# IRF7317_TC4427.net
KiCad netlist of a schematic drawn in Altium Designer
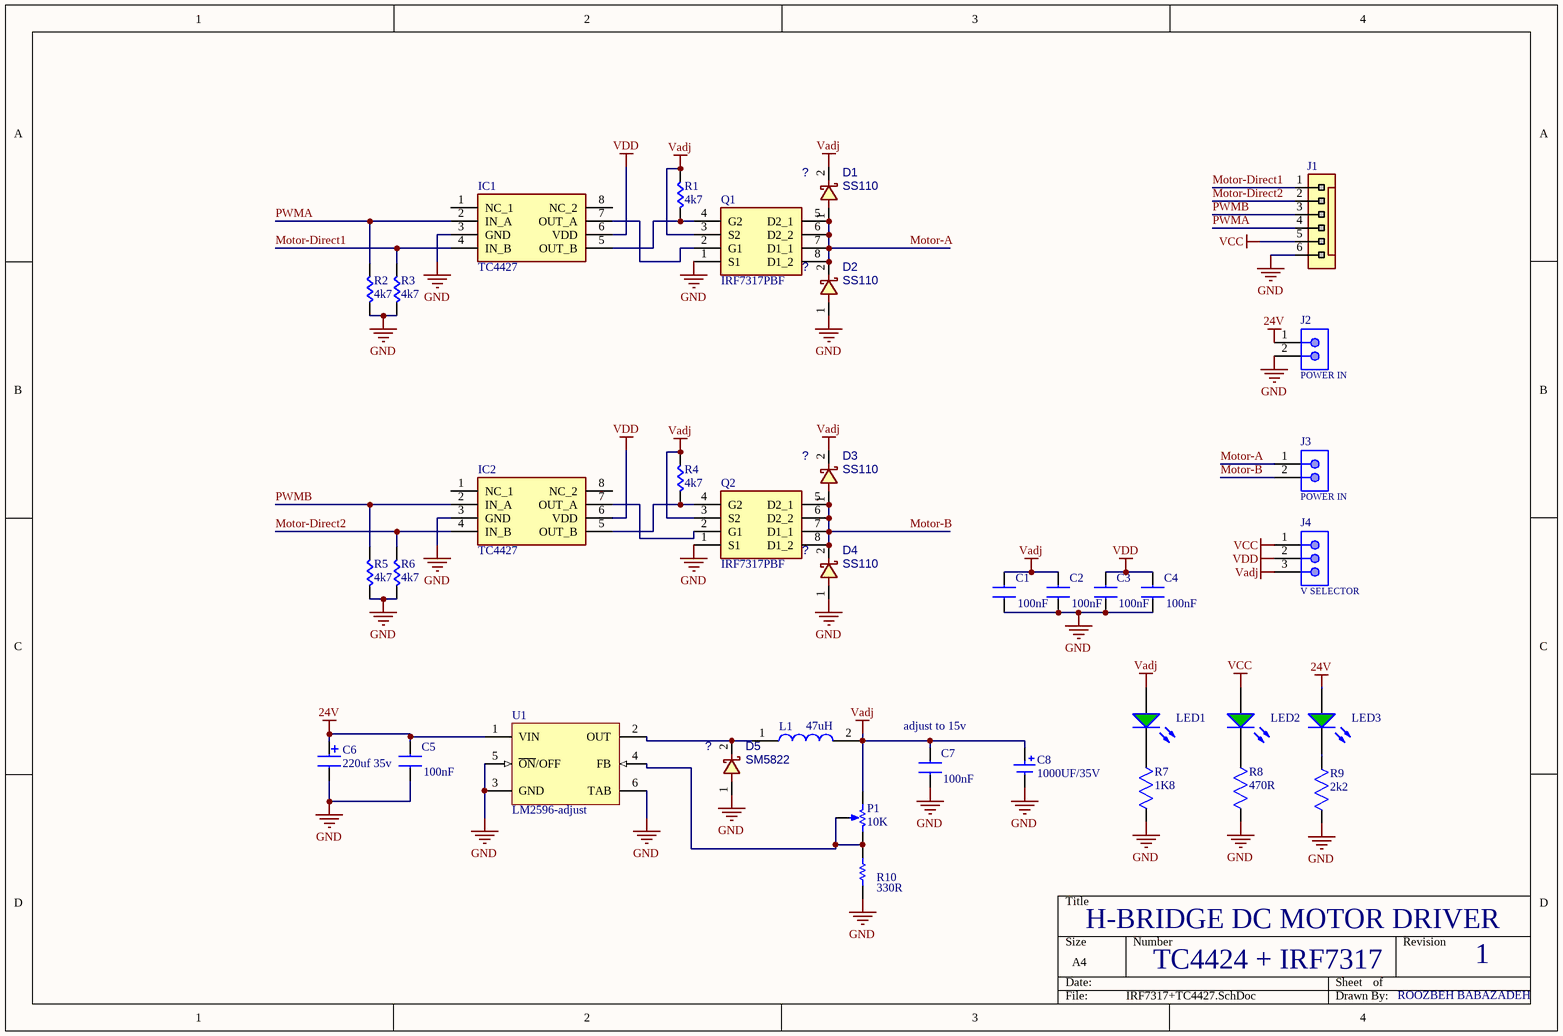
[diagram p0: IRF7317+TC4427.SchDoc]

(export (version "E")
  (design (tool "Eeschema 10.0.6"))
  (components
    (comp (ref "C1") (value "100nF") (footprint "C0805") (libsource (lib "OTHER") (part "C")))
    (comp (ref "C2") (value "100nF") (footprint "C0805") (libsource (lib "OTHER") (part "C")))
    (comp (ref "C3") (value "100nF") (footprint "C0805") (libsource (lib "OTHER") (part "C")))
    (comp (ref "C4") (value "100nF") (footprint "C0805") (libsource (lib "OTHER") (part "C")))
    (comp (ref "C5") (value "100nF") (footprint "C0805") (libsource (lib "OTHER") (part "C")))
    (comp (ref "C6") (value "220uf 35v") (footprint "C_EL_10X12") (libsource (lib "OTHER") (part "CAP3528")))
    (comp (ref "C7") (value "100nF") (footprint "C0805") (libsource (lib "OTHER") (part "C")))
    (comp (ref "C8")
      (value "1000UF/35V")
      (footprint "C_EL_12X25")
      (libsource (lib "OTHER") (part "CAP_ELECTRO_POLIMER"))
    )
    (comp (ref "D1")
      (value "SS110")
      (footprint "D_SMA")
      (description "DIODE, SCHOTTKY, 40V, 1A")
      (fields
        (field (name "MANF") "DIODES")
        (field (name "MANF_P#") "1N5819HW-7-F")
        (field (name "ALTIUM_VALUE") "?")
      )
      (libsource (lib "diode") (part "SCHOTTKY"))
    )
    (comp (ref "D2")
      (value "SS110")
      (footprint "D_SMA")
      (description "DIODE, SCHOTTKY, 40V, 1A")
      (fields
        (field (name "MANF") "DIODES")
        (field (name "MANF_P#") "1N5819HW-7-F")
        (field (name "ALTIUM_VALUE") "?")
      )
      (libsource (lib "diode") (part "SCHOTTKY"))
    )
    (comp (ref "D3")
      (value "SS110")
      (footprint "D_SMA")
      (description "DIODE, SCHOTTKY, 40V, 1A")
      (fields
        (field (name "MANF") "DIODES")
        (field (name "MANF_P#") "1N5819HW-7-F")
        (field (name "ALTIUM_VALUE") "?")
      )
      (libsource (lib "diode") (part "SCHOTTKY"))
    )
    (comp (ref "D4")
      (value "SS110")
      (footprint "D_SMA")
      (description "DIODE, SCHOTTKY, 40V, 1A")
      (fields
        (field (name "MANF") "DIODES")
        (field (name "MANF_P#") "1N5819HW-7-F")
        (field (name "ALTIUM_VALUE") "?")
      )
      (libsource (lib "diode") (part "SCHOTTKY"))
    )
    (comp (ref "D5")
      (value "SM5822")
      (footprint "D_SMB")
      (description "DIODE, SCHOTTKY, 40V, 1A")
      (fields
        (field (name "MANF") "DIODES")
        (field (name "MANF_P#") "1N5819HW-7-F")
        (field (name "ALTIUM_VALUE") "?")
      )
      (libsource (lib "diode") (part "SCHOTTKY"))
    )
    (comp (ref "IC1")
      (value "TC4427")
      (footprint "SO_8")
      (description "Integrated Circuit")
      (fields
        (field (name "MANUFACTURER_PART_NUMBER") "TC4427EOA713")
        (field (name "MOUSER PART NUMBER") "579-TC4427EOA713")
      )
      (libsource (lib "*") (part "TC4427EOA713"))
    )
    (comp (ref "IC2")
      (value "TC4427")
      (footprint "SO_8")
      (description "Integrated Circuit")
      (fields
        (field (name "MANUFACTURER_PART_NUMBER") "TC4427EOA713")
        (field (name "MOUSER PART NUMBER") "579-TC4427EOA713")
      )
      (libsource (lib "*") (part "TC4427EOA713"))
    )
    (comp (ref "J1")
      (value "HDRWF_6")
      (footprint "WF_6")
      (description "Header, WF, Pitch: 2.54mm")
      (libsource (lib "xh-xhr-wf-hhdr-hh6r") (part "HDRWF_6"))
    )
    (comp (ref "J2")
      (value "POWER IN")
      (footprint "PWL_2")
      (description "WR-PHD Pin Header, THT, pitch 2.54mm, Single Row, Vertical, 2pin")
      (fields (field (name "PART NUMBER") "61300211121") (field (name "PUBLISHER") "Wurth Elektronik"))
      (libsource (lib "sip m") (part "sip 2"))
    )
    (comp (ref "J3")
      (value "POWER IN")
      (footprint "PWL_2")
      (description "WR-PHD Pin Header, THT, pitch 2.54mm, Single Row, Vertical, 2pin")
      (fields (field (name "PART NUMBER") "61300211121") (field (name "PUBLISHER") "Wurth Elektronik"))
      (libsource (lib "sip m") (part "sip 2"))
    )
    (comp (ref "J4")
      (value "V SELECTOR")
      (footprint "3_SIP")
      (description "WR-PHD Pin Header, THT, pitch 2.54mm, Single Row, Vertical, 3pin")
      (fields (field (name "PART NUMBER") "61300311121") (field (name "PUBLISHER") "Wurth Elektronik"))
      (libsource (lib "sip m") (part "sip 3"))
    )
    (comp (ref "L1")
      (value "47uH")
      (footprint "CDRH127LDNP560MC-12*12")
      (description "Inductor")
      (fields
        (field (name "MANUFACTURER_PART_NUMBER") "CDRH127/LDNP-560MC")
        (field (name "MOUSER PART NUMBER") "851-CDRH127LDNP560MC")
      )
      (libsource (lib "*") (part "CDRH127_LDNP-560MC"))
    )
    (comp (ref "LED1") (value "~") (footprint "LED1206RED") (libsource (lib "OTHER") (part "LED3mm")))
    (comp (ref "LED2") (value "~") (footprint "LED1206RED") (libsource (lib "OTHER") (part "LED3mm")))
    (comp (ref "LED3") (value "~") (footprint "LED1206RED") (libsource (lib "OTHER") (part "LED3mm")))
    (comp (ref "P1")
      (value "10K")
      (footprint "POT_3296W")
      (description "Potentiometer")
      (libsource (lib "My_LIB") (part "Multi-Turn"))
    )
    (comp (ref "Q1")
      (value "IRF7317PBF")
      (footprint "SO_8")
      (description "Transistor")
      (fields (field (name "MOUSER PART NUMBER") "942-IRF7317PBF"))
      (libsource (lib "*") (part "IRF7317PBF"))
    )
    (comp (ref "Q2")
      (value "IRF7317PBF")
      (footprint "SO_8")
      (description "Transistor")
      (fields (field (name "MOUSER PART NUMBER") "942-IRF7317PBF"))
      (libsource (lib "*") (part "IRF7317PBF"))
    )
    (comp (ref "R1") (value "4k7") (footprint "R0805") (libsource (lib "OTHER") (part "R")))
    (comp (ref "R2") (value "4k7") (footprint "R0805") (libsource (lib "OTHER") (part "R")))
    (comp (ref "R3") (value "4k7") (footprint "R0805") (libsource (lib "OTHER") (part "R")))
    (comp (ref "R4") (value "4k7") (footprint "R0805") (libsource (lib "OTHER") (part "R")))
    (comp (ref "R5") (value "4k7") (footprint "R0805") (libsource (lib "OTHER") (part "R")))
    (comp (ref "R6") (value "4k7") (footprint "R0805") (libsource (lib "OTHER") (part "R")))
    (comp (ref "R7") (value "1K8") (footprint "R0805") (libsource (lib "") (part "R_1")))
    (comp (ref "R8") (value "470R") (footprint "R0805") (libsource (lib "") (part "R_1")))
    (comp (ref "R9") (value "2k2") (footprint "R0805") (libsource (lib "") (part "R_1")))
    (comp (ref "R10")
      (value "330R")
      (footprint "R0805")
      (description "Resistor")
      (fields (field (name "PUBLISHER") "Altium Limited"))
      (libsource (lib "Miscellaneous Devices") (part "Res1"))
    )
    (comp (ref "U1")
      (value "LM2596-adjust")
      (footprint "to-263-5 5d2pak LM2596S")
      (libsource (lib "POWER") (part "LM2596s"))
    )
  )
  (nets
    (net (code "1") (name "/Motor-A") (class "Default")
      (node (ref "D1") (pin "1") (pinfunction "1_1") (pintype "passive"))
      (node (ref "D2") (pin "2") (pinfunction "2_2") (pintype "passive"))
      (node (ref "J3") (pin "1") (pinfunction "1_1") (pintype "passive"))
      (node (ref "Q1") (pin "5") (pinfunction "D2_1_5") (pintype "passive"))
      (node (ref "Q1") (pin "6") (pinfunction "D2_2_6") (pintype "passive"))
      (node (ref "Q1") (pin "7") (pinfunction "D1_1_7") (pintype "passive"))
      (node (ref "Q1") (pin "8") (pinfunction "D1_2_8") (pintype "passive"))
    )
    (net (code "2") (name "/Motor-B") (class "Default")
      (node (ref "D3") (pin "1") (pinfunction "1_1") (pintype "passive"))
      (node (ref "D4") (pin "2") (pinfunction "2_2") (pintype "passive"))
      (node (ref "J3") (pin "2") (pinfunction "2_2") (pintype "passive"))
      (node (ref "Q2") (pin "5") (pinfunction "D2_1_5") (pintype "passive"))
      (node (ref "Q2") (pin "6") (pinfunction "D2_2_6") (pintype "passive"))
      (node (ref "Q2") (pin "7") (pinfunction "D1_1_7") (pintype "passive"))
      (node (ref "Q2") (pin "8") (pinfunction "D1_2_8") (pintype "passive"))
    )
    (net (code "3") (name "/Motor-Direct1") (class "Default")
      (node (ref "IC1") (pin "4") (pinfunction "IN_B_4") (pintype "passive"))
      (node (ref "J1") (pin "1") (pinfunction "1_1") (pintype "passive"))
      (node (ref "R3") (pin "1") (pintype "passive"))
    )
    (net (code "4") (name "/Motor-Direct2") (class "Default")
      (node (ref "IC2") (pin "4") (pinfunction "IN_B_4") (pintype "passive"))
      (node (ref "J1") (pin "2") (pinfunction "2_2") (pintype "passive"))
      (node (ref "R6") (pin "1") (pintype "passive"))
    )
    (net (code "5") (name "/PWMA") (class "Default")
      (node (ref "IC1") (pin "2") (pinfunction "IN_A_2") (pintype "passive"))
      (node (ref "J1") (pin "4") (pinfunction "4_4") (pintype "passive"))
      (node (ref "R2") (pin "1") (pintype "passive"))
    )
    (net (code "6") (name "/PWMB") (class "Default")
      (node (ref "IC2") (pin "2") (pinfunction "IN_A_2") (pintype "passive"))
      (node (ref "J1") (pin "3") (pinfunction "3_3") (pintype "passive"))
      (node (ref "R5") (pin "1") (pintype "passive"))
    )
    (net (code "7") (name "24V") (class "Default")
      (node (ref "C5") (pin "2") (pintype "passive"))
      (node (ref "C6") (pin "1") (pinfunction "1_1") (pintype "passive"))
      (node (ref "J2") (pin "1") (pinfunction "1_1") (pintype "passive"))
      (node (ref "LED3") (pin "1") (pinfunction "A_1") (pintype "passive"))
      (node (ref "U1") (pin "1") (pinfunction "VIN_1") (pintype "power_in"))
    )
    (net (code "8") (name "GND") (class "Default")
      (node (ref "C1") (pin "1") (pintype "passive"))
      (node (ref "C2") (pin "1") (pintype "passive"))
      (node (ref "C3") (pin "1") (pintype "passive"))
      (node (ref "C4") (pin "1") (pintype "passive"))
      (node (ref "C5") (pin "1") (pintype "passive"))
      (node (ref "C6") (pin "2") (pinfunction "2_2") (pintype "passive"))
      (node (ref "C7") (pin "1") (pintype "passive"))
      (node (ref "C8") (pin "2") (pinfunction "2_2") (pintype "passive"))
      (node (ref "D2") (pin "1") (pinfunction "1_1") (pintype "passive"))
      (node (ref "D4") (pin "1") (pinfunction "1_1") (pintype "passive"))
      (node (ref "D5") (pin "1") (pinfunction "1_1") (pintype "passive"))
      (node (ref "IC1") (pin "3") (pinfunction "GND_3") (pintype "passive"))
      (node (ref "IC2") (pin "3") (pinfunction "GND_3") (pintype "passive"))
      (node (ref "J1") (pin "6") (pinfunction "6_6") (pintype "passive"))
      (node (ref "J2") (pin "2") (pinfunction "2_2") (pintype "passive"))
      (node (ref "Q1") (pin "1") (pinfunction "S1_1") (pintype "passive"))
      (node (ref "Q2") (pin "1") (pinfunction "S1_1") (pintype "passive"))
      (node (ref "R10") (pin "1") (pinfunction "1_1") (pintype "passive"))
      (node (ref "R2") (pin "2") (pintype "passive"))
      (node (ref "R3") (pin "2") (pintype "passive"))
      (node (ref "R5") (pin "2") (pintype "passive"))
      (node (ref "R6") (pin "2") (pintype "passive"))
      (node (ref "R7") (pin "2") (pintype "passive"))
      (node (ref "R8") (pin "2") (pintype "passive"))
      (node (ref "R9") (pin "2") (pintype "passive"))
      (node (ref "U1") (pin "3") (pinfunction "GND_3") (pintype "power_in"))
      (node (ref "U1") (pin "5") (pinfunction "~{ON}/OFF_5") (pintype "input"))
      (node (ref "U1") (pin "6") (pinfunction "TAB_6") (pintype "power_in"))
    )
    (net (code "9") (name "Net-(IC1-OUT_A)") (class "Default")
      (node (ref "IC1") (pin "7") (pinfunction "OUT_A_7") (pintype "passive"))
      (node (ref "Q1") (pin "2") (pinfunction "G1_2") (pintype "passive"))
    )
    (net (code "10") (name "Net-(IC1-OUT_B)") (class "Default")
      (node (ref "IC1") (pin "5") (pinfunction "OUT_B_5") (pintype "passive"))
      (node (ref "Q1") (pin "4") (pinfunction "G2_4") (pintype "passive"))
      (node (ref "R1") (pin "2") (pintype "passive"))
    )
    (net (code "11") (name "Net-(IC2-OUT_A)") (class "Default")
      (node (ref "IC2") (pin "7") (pinfunction "OUT_A_7") (pintype "passive"))
      (node (ref "Q2") (pin "2") (pinfunction "G1_2") (pintype "passive"))
    )
    (net (code "12") (name "Net-(IC2-OUT_B)") (class "Default")
      (node (ref "IC2") (pin "5") (pinfunction "OUT_B_5") (pintype "passive"))
      (node (ref "Q2") (pin "4") (pinfunction "G2_4") (pintype "passive"))
      (node (ref "R4") (pin "2") (pintype "passive"))
    )
    (net (code "13") (name "Net-(LED1-K)") (class "Default")
      (node (ref "LED1") (pin "2") (pinfunction "K_2") (pintype "passive"))
      (node (ref "R7") (pin "1") (pintype "passive"))
    )
    (net (code "14") (name "Net-(LED2-K)") (class "Default")
      (node (ref "LED2") (pin "2") (pinfunction "K_2") (pintype "passive"))
      (node (ref "R8") (pin "1") (pintype "passive"))
    )
    (net (code "15") (name "Net-(LED3-K)") (class "Default")
      (node (ref "LED3") (pin "2") (pinfunction "K_2") (pintype "passive"))
      (node (ref "R9") (pin "1") (pintype "passive"))
    )
    (net (code "16") (name "Net-(P1-TAP)") (class "Default")
      (node (ref "P1") (pin "1") (pinfunction "TOP_1") (pintype "passive"))
      (node (ref "P1") (pin "2") (pinfunction "TAP_2") (pintype "passive"))
      (node (ref "R10") (pin "2") (pinfunction "2_2") (pintype "passive"))
      (node (ref "U1") (pin "4") (pinfunction "FB_4") (pintype "input"))
    )
    (net (code "17") (name "Net-(U1-OUT)") (class "Default")
      (node (ref "D5") (pin "2") (pinfunction "2_2") (pintype "passive"))
      (node (ref "L1") (pin "1") (pinfunction "1_1") (pintype "passive"))
      (node (ref "U1") (pin "2") (pinfunction "OUT_2") (pintype "power_in"))
    )
    (net (code "18") (name "VCC") (class "Default")
      (node (ref "J1") (pin "5") (pinfunction "5_5") (pintype "passive"))
      (node (ref "J4") (pin "1") (pinfunction "1_1") (pintype "passive"))
      (node (ref "LED2") (pin "1") (pinfunction "A_1") (pintype "passive"))
    )
    (net (code "19") (name "VDD") (class "Default")
      (node (ref "C3") (pin "2") (pintype "passive"))
      (node (ref "C4") (pin "2") (pintype "passive"))
      (node (ref "IC1") (pin "6") (pinfunction "VDD_6") (pintype "passive"))
      (node (ref "IC2") (pin "6") (pinfunction "VDD_6") (pintype "passive"))
      (node (ref "J4") (pin "2") (pinfunction "2_2") (pintype "passive"))
    )
    (net (code "20") (name "Vadj") (class "Default")
      (node (ref "C1") (pin "2") (pintype "passive"))
      (node (ref "C2") (pin "2") (pintype "passive"))
      (node (ref "C7") (pin "2") (pintype "passive"))
      (node (ref "C8") (pin "1") (pinfunction "1_1") (pintype "passive"))
      (node (ref "D1") (pin "2") (pinfunction "2_2") (pintype "passive"))
      (node (ref "D3") (pin "2") (pinfunction "2_2") (pintype "passive"))
      (node (ref "J4") (pin "3") (pinfunction "3_3") (pintype "passive"))
      (node (ref "L1") (pin "2") (pinfunction "2_2") (pintype "passive"))
      (node (ref "LED1") (pin "1") (pinfunction "A_1") (pintype "passive"))
      (node (ref "P1") (pin "3") (pinfunction "BOT_3") (pintype "passive"))
      (node (ref "Q1") (pin "3") (pinfunction "S2_3") (pintype "passive"))
      (node (ref "Q2") (pin "3") (pinfunction "S2_3") (pintype "passive"))
      (node (ref "R1") (pin "1") (pintype "passive"))
      (node (ref "R4") (pin "1") (pintype "passive"))
    )
    (net (code "21") (name "unconnected-(IC1-NC_1-Pad1)") (class "Default")
      (node (ref "IC1") (pin "1") (pinfunction "NC_1_1") (pintype "passive"))
    )
    (net (code "22") (name "unconnected-(IC1-NC_2-Pad8)") (class "Default")
      (node (ref "IC1") (pin "8") (pinfunction "NC_2_8") (pintype "passive"))
    )
    (net (code "23") (name "unconnected-(IC2-NC_1-Pad1)") (class "Default")
      (node (ref "IC2") (pin "1") (pinfunction "NC_1_1") (pintype "passive"))
    )
    (net (code "24") (name "unconnected-(IC2-NC_2-Pad8)") (class "Default")
      (node (ref "IC2") (pin "8") (pinfunction "NC_2_8") (pintype "passive"))
    )
  )
)
